# SDRAM.net
KiCad netlist of a schematic drawn in Altium Designer
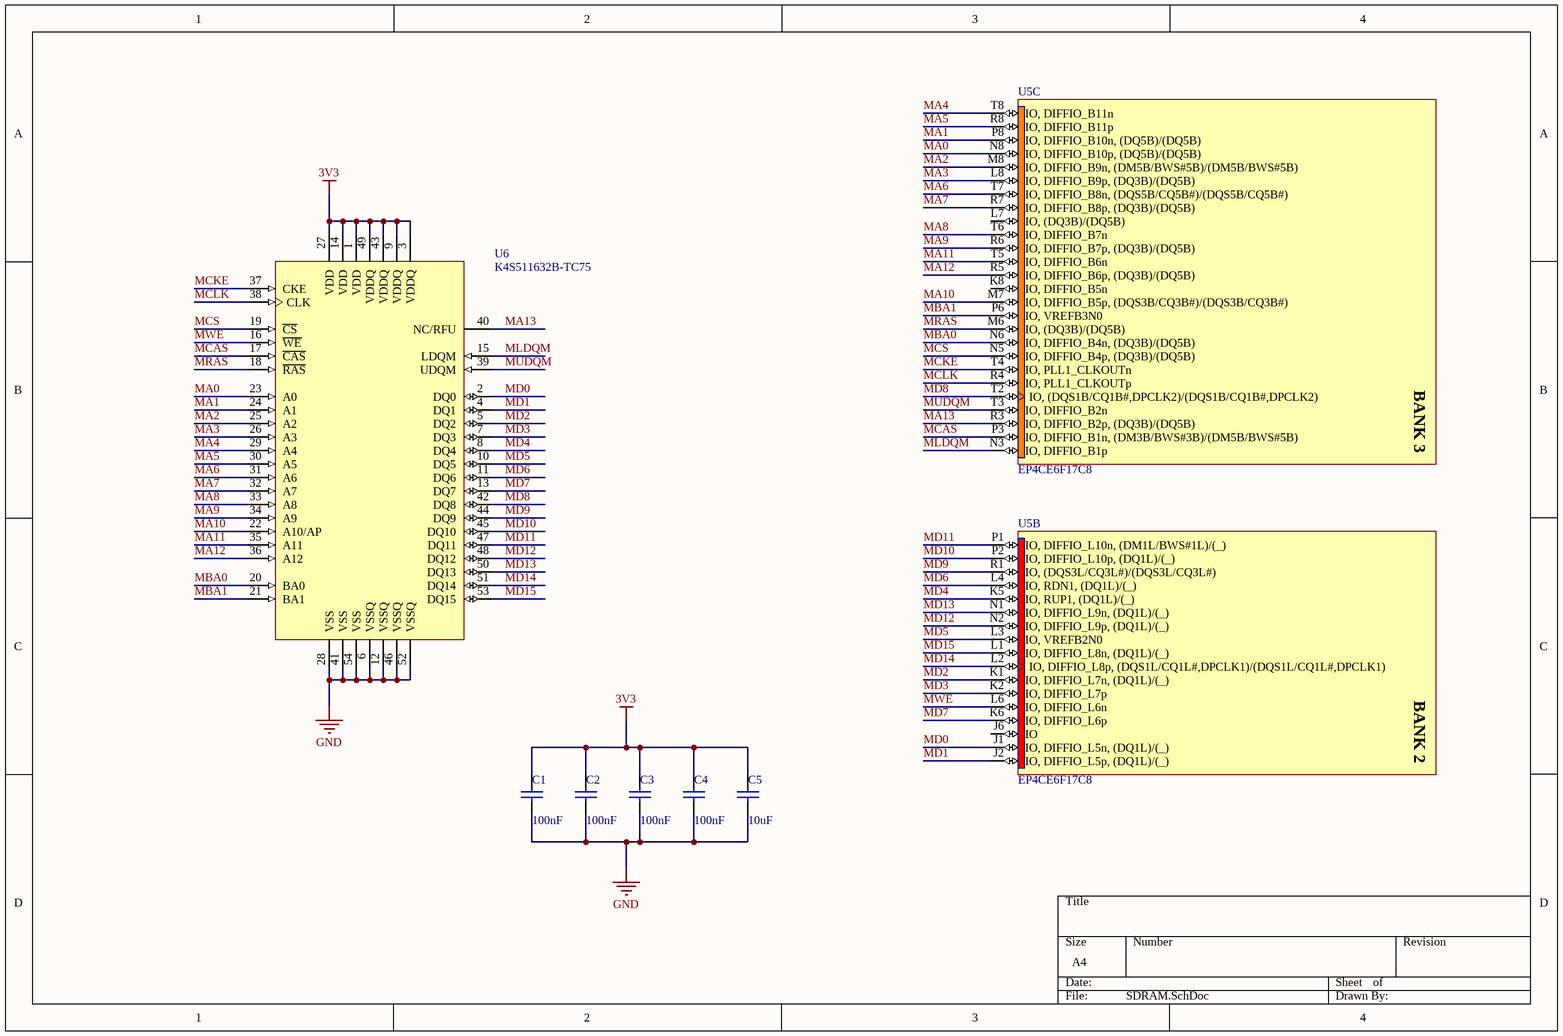
[diagram p0: SDRAM.SchDoc]

(export (version "E")
  (design (tool "Eeschema 10.0.6"))
  (components
    (comp (ref "C1")
      (value "100nF")
      (footprint "C0603")
      (description "Capacitor")
      (fields (field (name "PUBLISHER") "Altium Limited"))
      (libsource (lib "Miscellaneous Devices") (part "Cap"))
    )
    (comp (ref "C2")
      (value "100nF")
      (footprint "C0603")
      (description "Capacitor")
      (fields (field (name "PUBLISHER") "Altium Limited"))
      (libsource (lib "Miscellaneous Devices") (part "Cap"))
    )
    (comp (ref "C3")
      (value "100nF")
      (footprint "C0603")
      (description "Capacitor")
      (fields (field (name "PUBLISHER") "Altium Limited"))
      (libsource (lib "Miscellaneous Devices") (part "Cap"))
    )
    (comp (ref "C4")
      (value "100nF")
      (footprint "C0603")
      (description "Capacitor")
      (fields (field (name "PUBLISHER") "Altium Limited"))
      (libsource (lib "Miscellaneous Devices") (part "Cap"))
    )
    (comp (ref "C5")
      (value "10uF")
      (footprint "C1206")
      (description "Capacitor")
      (fields (field (name "PUBLISHER") "Altium Limited"))
      (libsource (lib "Miscellaneous Devices") (part "Cap"))
    )
    (comp (ref "U5")
      (value "EP4CE6F17C8")
      (footprint "FBGA256")
      (fields (field (name "PUBLISHER") "Altium Limited"))
      (libsource (lib "Altera Cyclone IV E") (part "EP4CE6F17C8"))
    )
    (comp (ref "U6")
      (value "K4S511632B-TC75")
      (footprint "54_TSOP2_400AF_N")
      (description "512Mb Synchronous High Data Rate DRAM, 8Mb x 16Bit x 4 Banks, 54-Pin TSOP")
      (fields (field (name "PUBLISHER") "Altium Limited"))
      (libsource (lib "Samsung Memory Dynamic RAM") (part "K4S511632B-TC75"))
    )
  )
  (nets
    (net (code "1") (name "/MA0") (class "Default")
      (node (ref "U5") (pin "N8") (pinfunction "IO,_DIFFIO_B10p,_(DQ5B)/(DQ5B)_N8") (pintype "bidirectional"))
      (node (ref "U6") (pin "23") (pinfunction "A0_23") (pintype "input"))
    )
    (net (code "2") (name "/MA1") (class "Default")
      (node (ref "U5") (pin "P8") (pinfunction "IO,_DIFFIO_B10n,_(DQ5B)/(DQ5B)_P8") (pintype "bidirectional"))
      (node (ref "U6") (pin "24") (pinfunction "A1_24") (pintype "input"))
    )
    (net (code "3") (name "/MA2") (class "Default")
      (node (ref "U5") (pin "M8") (pinfunction "IO,_DIFFIO_B9n,_(DM5B/BWS#5B)/(DM5B/BWS#5B)_M8") (pintype "bidirectional"))
      (node (ref "U6") (pin "25") (pinfunction "A2_25") (pintype "input"))
    )
    (net (code "4") (name "/MA3") (class "Default")
      (node (ref "U5") (pin "L8") (pinfunction "IO,_DIFFIO_B9p,_(DQ3B)/(DQ5B)_L8") (pintype "bidirectional"))
      (node (ref "U6") (pin "26") (pinfunction "A3_26") (pintype "input"))
    )
    (net (code "5") (name "/MA4") (class "Default")
      (node (ref "U5") (pin "T8") (pinfunction "IO,_DIFFIO_B11n_T8") (pintype "bidirectional"))
      (node (ref "U6") (pin "29") (pinfunction "A4_29") (pintype "input"))
    )
    (net (code "6") (name "/MA5") (class "Default")
      (node (ref "U5") (pin "R8") (pinfunction "IO,_DIFFIO_B11p_R8") (pintype "bidirectional"))
      (node (ref "U6") (pin "30") (pinfunction "A5_30") (pintype "input"))
    )
    (net (code "7") (name "/MA6") (class "Default")
      (node (ref "U5") (pin "T7") (pinfunction "IO,_DIFFIO_B8n,_(DQS5B/CQ5B#)/(DQS5B/CQ5B#)_T7") (pintype "bidirectional"))
      (node (ref "U6") (pin "31") (pinfunction "A6_31") (pintype "input"))
    )
    (net (code "8") (name "/MA7") (class "Default")
      (node (ref "U5") (pin "R7") (pinfunction "IO,_DIFFIO_B8p,_(DQ3B)/(DQ5B)_R7") (pintype "bidirectional"))
      (node (ref "U6") (pin "32") (pinfunction "A7_32") (pintype "input"))
    )
    (net (code "9") (name "/MA8") (class "Default")
      (node (ref "U5") (pin "T6") (pinfunction "IO,_DIFFIO_B7n_T6") (pintype "bidirectional"))
      (node (ref "U6") (pin "33") (pinfunction "A8_33") (pintype "input"))
    )
    (net (code "10") (name "/MA9") (class "Default")
      (node (ref "U5") (pin "R6") (pinfunction "IO,_DIFFIO_B7p,_(DQ3B)/(DQ5B)_R6") (pintype "bidirectional"))
      (node (ref "U6") (pin "34") (pinfunction "A9_34") (pintype "input"))
    )
    (net (code "11") (name "/MA10") (class "Default")
      (node (ref "U5") (pin "M7") (pinfunction "IO,_DIFFIO_B5p,_(DQS3B/CQ3B#)/(DQS3B/CQ3B#)_M7") (pintype "bidirectional"))
      (node (ref "U6") (pin "22") (pinfunction "A10/AP_22") (pintype "input"))
    )
    (net (code "12") (name "/MA11") (class "Default")
      (node (ref "U5") (pin "T5") (pinfunction "IO,_DIFFIO_B6n_T5") (pintype "bidirectional"))
      (node (ref "U6") (pin "35") (pinfunction "A11_35") (pintype "input"))
    )
    (net (code "13") (name "/MA12") (class "Default")
      (node (ref "U5") (pin "R5") (pinfunction "IO,_DIFFIO_B6p,_(DQ3B)/(DQ5B)_R5") (pintype "bidirectional"))
      (node (ref "U6") (pin "36") (pinfunction "A12_36") (pintype "input"))
    )
    (net (code "14") (name "/MA13") (class "Default")
      (node (ref "U5") (pin "R3") (pinfunction "IO,_DIFFIO_B2p,_(DQ3B)/(DQ5B)_R3") (pintype "bidirectional"))
      (node (ref "U6") (pin "40") (pinfunction "NC/RFU_40") (pintype "passive"))
    )
    (net (code "15") (name "/MBA0") (class "Default")
      (node (ref "U5") (pin "N6") (pinfunction "IO,_DIFFIO_B4n,_(DQ3B)/(DQ5B)_N6") (pintype "bidirectional"))
      (node (ref "U6") (pin "20") (pinfunction "BA0_20") (pintype "input"))
    )
    (net (code "16") (name "/MBA1") (class "Default")
      (node (ref "U5") (pin "P6") (pinfunction "IO,_VREFB3N0_P6") (pintype "bidirectional"))
      (node (ref "U6") (pin "21") (pinfunction "BA1_21") (pintype "input"))
    )
    (net (code "17") (name "/MCAS") (class "Default")
      (node (ref "U5") (pin "P3") (pinfunction "IO,_DIFFIO_B1n,_(DM3B/BWS#3B)/(DM5B/BWS#5B)_P3") (pintype "bidirectional"))
      (node (ref "U6") (pin "17") (pinfunction "~{CAS}_17") (pintype "input"))
    )
    (net (code "18") (name "/MCKE") (class "Default")
      (node (ref "U5") (pin "T4") (pinfunction "IO,_PLL1_CLKOUTn_T4") (pintype "bidirectional"))
      (node (ref "U6") (pin "37") (pinfunction "CKE_37") (pintype "input"))
    )
    (net (code "19") (name "/MCLK") (class "Default")
      (node (ref "U5") (pin "R4") (pinfunction "IO,_PLL1_CLKOUTp_R4") (pintype "bidirectional"))
      (node (ref "U6") (pin "38") (pinfunction "CLK_38") (pintype "input"))
    )
    (net (code "20") (name "/MCS") (class "Default")
      (node (ref "U5") (pin "N5") (pinfunction "IO,_DIFFIO_B4p,_(DQ3B)/(DQ5B)_N5") (pintype "bidirectional"))
      (node (ref "U6") (pin "19") (pinfunction "~{CS}_19") (pintype "input"))
    )
    (net (code "21") (name "/MD0") (class "Default")
      (node (ref "U5") (pin "J1") (pinfunction "IO,_DIFFIO_L5n,_(DQ1L)/(_)_J1") (pintype "bidirectional"))
      (node (ref "U6") (pin "2") (pinfunction "DQ0_2") (pintype "bidirectional"))
    )
    (net (code "22") (name "/MD1") (class "Default")
      (node (ref "U5") (pin "J2") (pinfunction "IO,_DIFFIO_L5p,_(DQ1L)/(_)_J2") (pintype "bidirectional"))
      (node (ref "U6") (pin "4") (pinfunction "DQ1_4") (pintype "bidirectional"))
    )
    (net (code "23") (name "/MD2") (class "Default")
      (node (ref "U5") (pin "K1") (pinfunction "IO,_DIFFIO_L7n,_(DQ1L)/(_)_K1") (pintype "bidirectional"))
      (node (ref "U6") (pin "5") (pinfunction "DQ2_5") (pintype "bidirectional"))
    )
    (net (code "24") (name "/MD3") (class "Default")
      (node (ref "U5") (pin "K2") (pinfunction "IO,_DIFFIO_L7p_K2") (pintype "bidirectional"))
      (node (ref "U6") (pin "7") (pinfunction "DQ3_7") (pintype "bidirectional"))
    )
    (net (code "25") (name "/MD4") (class "Default")
      (node (ref "U5") (pin "K5") (pinfunction "IO,_RUP1,_(DQ1L)/(_)_K5") (pintype "bidirectional"))
      (node (ref "U6") (pin "8") (pinfunction "DQ4_8") (pintype "bidirectional"))
    )
    (net (code "26") (name "/MD5") (class "Default")
      (node (ref "U5") (pin "L3") (pinfunction "IO,_VREFB2N0_L3") (pintype "bidirectional"))
      (node (ref "U6") (pin "10") (pinfunction "DQ5_10") (pintype "bidirectional"))
    )
    (net (code "27") (name "/MD6") (class "Default")
      (node (ref "U5") (pin "L4") (pinfunction "IO,_RDN1,_(DQ1L)/(_)_L4") (pintype "bidirectional"))
      (node (ref "U6") (pin "11") (pinfunction "DQ6_11") (pintype "bidirectional"))
    )
    (net (code "28") (name "/MD7") (class "Default")
      (node (ref "U5") (pin "K6") (pinfunction "IO,_DIFFIO_L6p_K6") (pintype "bidirectional"))
      (node (ref "U6") (pin "13") (pinfunction "DQ7_13") (pintype "bidirectional"))
    )
    (net (code "29") (name "/MD8") (class "Default")
      (node (ref "U5") (pin "T2") (pinfunction "IO,_(DQS1B/CQ1B#,DPCLK2)/(DQS1B/CQ1B#,DPCLK2)_T2") (pintype "bidirectional"))
      (node (ref "U6") (pin "42") (pinfunction "DQ8_42") (pintype "bidirectional"))
    )
    (net (code "30") (name "/MD9") (class "Default")
      (node (ref "U5") (pin "R1") (pinfunction "IO,_(DQS3L/CQ3L#)/(DQS3L/CQ3L#)_R1") (pintype "bidirectional"))
      (node (ref "U6") (pin "44") (pinfunction "DQ9_44") (pintype "bidirectional"))
    )
    (net (code "31") (name "/MD10") (class "Default")
      (node (ref "U5") (pin "P2") (pinfunction "IO,_DIFFIO_L10p,_(DQ1L)/(_)_P2") (pintype "bidirectional"))
      (node (ref "U6") (pin "45") (pinfunction "DQ10_45") (pintype "bidirectional"))
    )
    (net (code "32") (name "/MD11") (class "Default")
      (node (ref "U5") (pin "P1") (pinfunction "IO,_DIFFIO_L10n,_(DM1L/BWS#1L)/(_)_P1") (pintype "bidirectional"))
      (node (ref "U6") (pin "47") (pinfunction "DQ11_47") (pintype "bidirectional"))
    )
    (net (code "33") (name "/MD12") (class "Default")
      (node (ref "U5") (pin "N2") (pinfunction "IO,_DIFFIO_L9p,_(DQ1L)/(_)_N2") (pintype "bidirectional"))
      (node (ref "U6") (pin "48") (pinfunction "DQ12_48") (pintype "bidirectional"))
    )
    (net (code "34") (name "/MD13") (class "Default")
      (node (ref "U5") (pin "N1") (pinfunction "IO,_DIFFIO_L9n,_(DQ1L)/(_)_N1") (pintype "bidirectional"))
      (node (ref "U6") (pin "50") (pinfunction "DQ13_50") (pintype "bidirectional"))
    )
    (net (code "35") (name "/MD14") (class "Default")
      (node (ref "U5") (pin "L2") (pinfunction "IO,_DIFFIO_L8p,_(DQS1L/CQ1L#,DPCLK1)/(DQS1L/CQ1L#,DPCLK1)_L2") (pintype "bidirectional"))
      (node (ref "U6") (pin "51") (pinfunction "DQ14_51") (pintype "bidirectional"))
    )
    (net (code "36") (name "/MD15") (class "Default")
      (node (ref "U5") (pin "L1") (pinfunction "IO,_DIFFIO_L8n,_(DQ1L)/(_)_L1") (pintype "bidirectional"))
      (node (ref "U6") (pin "53") (pinfunction "DQ15_53") (pintype "bidirectional"))
    )
    (net (code "37") (name "/MLDQM") (class "Default")
      (node (ref "U5") (pin "N3") (pinfunction "IO,_DIFFIO_B1p_N3") (pintype "bidirectional"))
      (node (ref "U6") (pin "15") (pinfunction "LDQM_15") (pintype "input"))
    )
    (net (code "38") (name "/MRAS") (class "Default")
      (node (ref "U5") (pin "M6") (pinfunction "IO,_(DQ3B)/(DQ5B)_M6") (pintype "bidirectional"))
      (node (ref "U6") (pin "18") (pinfunction "~{RAS}_18") (pintype "input"))
    )
    (net (code "39") (name "/MUDQM") (class "Default")
      (node (ref "U5") (pin "T3") (pinfunction "IO,_DIFFIO_B2n_T3") (pintype "bidirectional"))
      (node (ref "U6") (pin "39") (pinfunction "UDQM_39") (pintype "input"))
    )
    (net (code "40") (name "/MWE") (class "Default")
      (node (ref "U5") (pin "L6") (pinfunction "IO,_DIFFIO_L6n_L6") (pintype "bidirectional"))
      (node (ref "U6") (pin "16") (pinfunction "~{WE}_16") (pintype "input"))
    )
    (net (code "41") (name "3V3") (class "Default")
      (node (ref "C1") (pin "2") (pinfunction "2_2") (pintype "passive"))
      (node (ref "C2") (pin "2") (pinfunction "2_2") (pintype "passive"))
      (node (ref "C3") (pin "2") (pinfunction "2_2") (pintype "passive"))
      (node (ref "C4") (pin "2") (pinfunction "2_2") (pintype "passive"))
      (node (ref "C5") (pin "1") (pinfunction "1_1") (pintype "passive"))
      (node (ref "U6") (pin "1") (pinfunction "VDD_1") (pintype "power_in"))
      (node (ref "U6") (pin "14") (pinfunction "VDD_14") (pintype "power_in"))
      (node (ref "U6") (pin "27") (pinfunction "VDD_27") (pintype "power_in"))
      (node (ref "U6") (pin "3") (pinfunction "VDDQ_3") (pintype "power_in"))
      (node (ref "U6") (pin "43") (pinfunction "VDDQ_43") (pintype "power_in"))
      (node (ref "U6") (pin "49") (pinfunction "VDDQ_49") (pintype "power_in"))
      (node (ref "U6") (pin "9") (pinfunction "VDDQ_9") (pintype "power_in"))
    )
    (net (code "42") (name "GND") (class "Default")
      (node (ref "C1") (pin "1") (pinfunction "1_1") (pintype "passive"))
      (node (ref "C2") (pin "1") (pinfunction "1_1") (pintype "passive"))
      (node (ref "C3") (pin "1") (pinfunction "1_1") (pintype "passive"))
      (node (ref "C4") (pin "1") (pinfunction "1_1") (pintype "passive"))
      (node (ref "C5") (pin "2") (pinfunction "2_2") (pintype "passive"))
      (node (ref "U6") (pin "12") (pinfunction "VSSQ_12") (pintype "power_in"))
      (node (ref "U6") (pin "28") (pinfunction "VSS_28") (pintype "power_in"))
      (node (ref "U6") (pin "41") (pinfunction "VSS_41") (pintype "power_in"))
      (node (ref "U6") (pin "46") (pinfunction "VSSQ_46") (pintype "power_in"))
      (node (ref "U6") (pin "52") (pinfunction "VSSQ_52") (pintype "power_in"))
      (node (ref "U6") (pin "54") (pinfunction "VSS_54") (pintype "power_in"))
      (node (ref "U6") (pin "6") (pinfunction "VSSQ_6") (pintype "power_in"))
    )
    (net (code "43") (name "unconnected-(U5B-IO-PadJ6)") (class "Default")
      (node (ref "U5") (pin "J6") (pinfunction "IO_J6") (pintype "bidirectional"))
    )
    (net (code "44") (name "unconnected-(U5C-IO,_(DQ3B){slash}(DQ5B)-PadL7)") (class "Default")
      (node (ref "U5") (pin "L7") (pinfunction "IO,_(DQ3B)/(DQ5B)_L7") (pintype "bidirectional"))
    )
    (net (code "45") (name "unconnected-(U5C-IO,_DIFFIO_B5n-PadK8)") (class "Default")
      (node (ref "U5") (pin "K8") (pinfunction "IO,_DIFFIO_B5n_K8") (pintype "bidirectional"))
    )
  )
)
